# VCNL4040.net
KiCad netlist of a schematic drawn in EAGLE
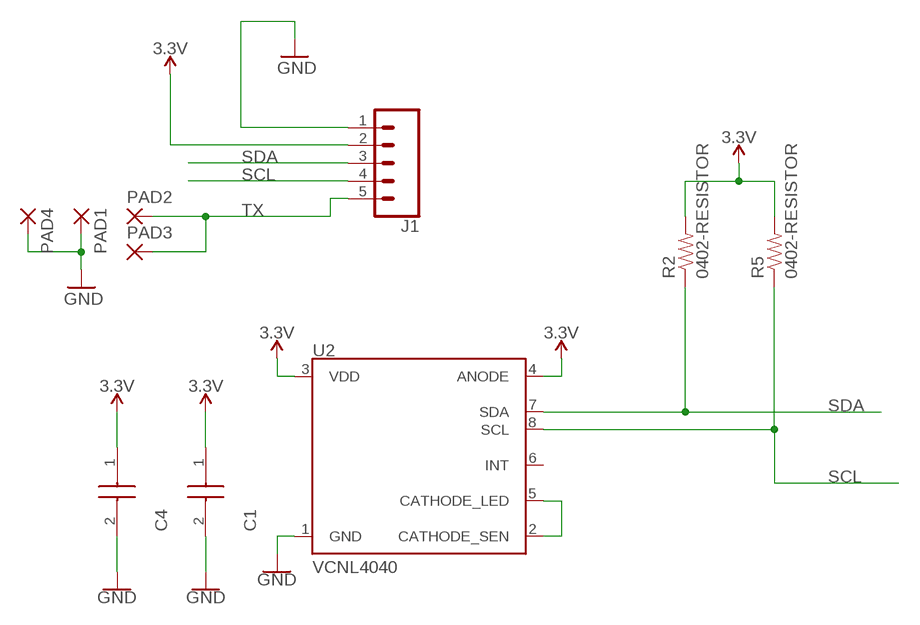
[diagram p0: schematic, sheet 1]

(export (version "E")
  (design (tool "Eeschema 10.0.6"))
  (components
    (comp (ref "C1")
      (value "0402-CAPCAPACITOR-0402")
      (footprint "eagle-import:CAPC1005X56N")
      (fields
        (field (name "MANUFACTURER_PART_NUMBER") "04026C105KAT2A")
        (field (name "MOUSER_PART_NUMBER") "581-04026C105KAT2A")
      )
      (libsource (lib "eagle-import") (part "0402-CAPCAPACITOR-0402"))
    )
    (comp (ref "C4")
      (value "0402-CAPCAPACITOR-0402")
      (footprint "eagle-import:CAPC1005X56N")
      (fields
        (field (name "MANUFACTURER_PART_NUMBER") "04026C105KAT2A")
        (field (name "MOUSER_PART_NUMBER") "581-04026C105KAT2A")
      )
      (libsource (lib "eagle-import") (part "0402-CAPCAPACITOR-0402"))
    )
    (comp (ref "J1")
      (value "CONN_051.27MM")
      (footprint "eagle-import:1X05_1.27MM")
      (libsource (lib "eagle-import") (part "CONN_051.27MM"))
    )
    (comp (ref "PAD1")
      (value "SMD2")
      (footprint "eagle-import:SMD1,27-2,54")
      (libsource (lib "eagle-import") (part "SMD2"))
    )
    (comp (ref "PAD2")
      (value "SMD2")
      (footprint "eagle-import:SMD1,27-2,54")
      (libsource (lib "eagle-import") (part "SMD2"))
    )
    (comp (ref "PAD3")
      (value "SMD2")
      (footprint "eagle-import:SMD1,27-2,54")
      (libsource (lib "eagle-import") (part "SMD2"))
    )
    (comp (ref "PAD4")
      (value "SMD2")
      (footprint "eagle-import:SMD1,27-2,54")
      (libsource (lib "eagle-import") (part "SMD2"))
    )
    (comp (ref "R2")
      (value "0402-RESISTOR")
      (footprint "eagle-import:0402")
      (libsource (lib "eagle-import") (part "RES_0402"))
    )
    (comp (ref "R5")
      (value "0402-RESISTOR")
      (footprint "eagle-import:0402")
      (libsource (lib "eagle-import") (part "RES_0402"))
    )
    (comp (ref "U2")
      (value "VCNL4040")
      (footprint "eagle-import:SPARKX_VCNL4040")
      (libsource (lib "eagle-import") (part "VCNL4040"))
    )
  )
  (nets
    (net (code "1") (name "/SCL") (class "Default")
      (node (ref "J1") (pin "4") (pinfunction "4_4") (pintype "passive"))
      (node (ref "R5") (pin "1") (pinfunction "1_1") (pintype "passive"))
      (node (ref "U2") (pin "8") (pinfunction "SCL_8") (pintype "bidirectional"))
    )
    (net (code "2") (name "/SDA") (class "Default")
      (node (ref "J1") (pin "3") (pinfunction "3_3") (pintype "passive"))
      (node (ref "R2") (pin "1") (pinfunction "1_1") (pintype "passive"))
      (node (ref "U2") (pin "7") (pinfunction "SDA_7") (pintype "bidirectional"))
    )
    (net (code "3") (name "/TX") (class "Default")
      (node (ref "J1") (pin "5") (pinfunction "5_5") (pintype "passive"))
      (node (ref "PAD2") (pin "1") (pinfunction "P_1") (pintype "passive"))
      (node (ref "PAD3") (pin "1") (pinfunction "P_1") (pintype "passive"))
    )
    (net (code "4") (name "3.3V") (class "Default")
      (node (ref "C1") (pin "1") (pinfunction "1_1") (pintype "bidirectional"))
      (node (ref "C4") (pin "1") (pinfunction "1_1") (pintype "bidirectional"))
      (node (ref "J1") (pin "2") (pinfunction "2_2") (pintype "passive"))
      (node (ref "R2") (pin "2") (pinfunction "2_2") (pintype "passive"))
      (node (ref "R5") (pin "2") (pinfunction "2_2") (pintype "passive"))
      (node (ref "U2") (pin "3") (pinfunction "VDD_3") (pintype "bidirectional"))
      (node (ref "U2") (pin "4") (pinfunction "ANODE_4") (pintype "bidirectional"))
    )
    (net (code "5") (name "GND") (class "Default")
      (node (ref "C1") (pin "2") (pinfunction "2_2") (pintype "bidirectional"))
      (node (ref "C4") (pin "2") (pinfunction "2_2") (pintype "bidirectional"))
      (node (ref "J1") (pin "1") (pinfunction "1_1") (pintype "passive"))
      (node (ref "PAD1") (pin "1") (pinfunction "P_1") (pintype "passive"))
      (node (ref "PAD4") (pin "1") (pinfunction "P_1") (pintype "passive"))
      (node (ref "U2") (pin "1") (pinfunction "GND_1") (pintype "bidirectional"))
    )
    (net (code "6") (name "Net-(U2-CATHODE_LED)") (class "Default")
      (node (ref "U2") (pin "2") (pinfunction "CATHODE_SEN_2") (pintype "bidirectional"))
      (node (ref "U2") (pin "5") (pinfunction "CATHODE_LED_5") (pintype "bidirectional"))
    )
    (net (code "7") (name "unconnected-(U2-INT-Pad6)") (class "Default")
      (node (ref "U2") (pin "6") (pinfunction "INT_6") (pintype "bidirectional"))
    )
  )
)
